# aspirin.net
KiCad netlist of a schematic drawn in EAGLE
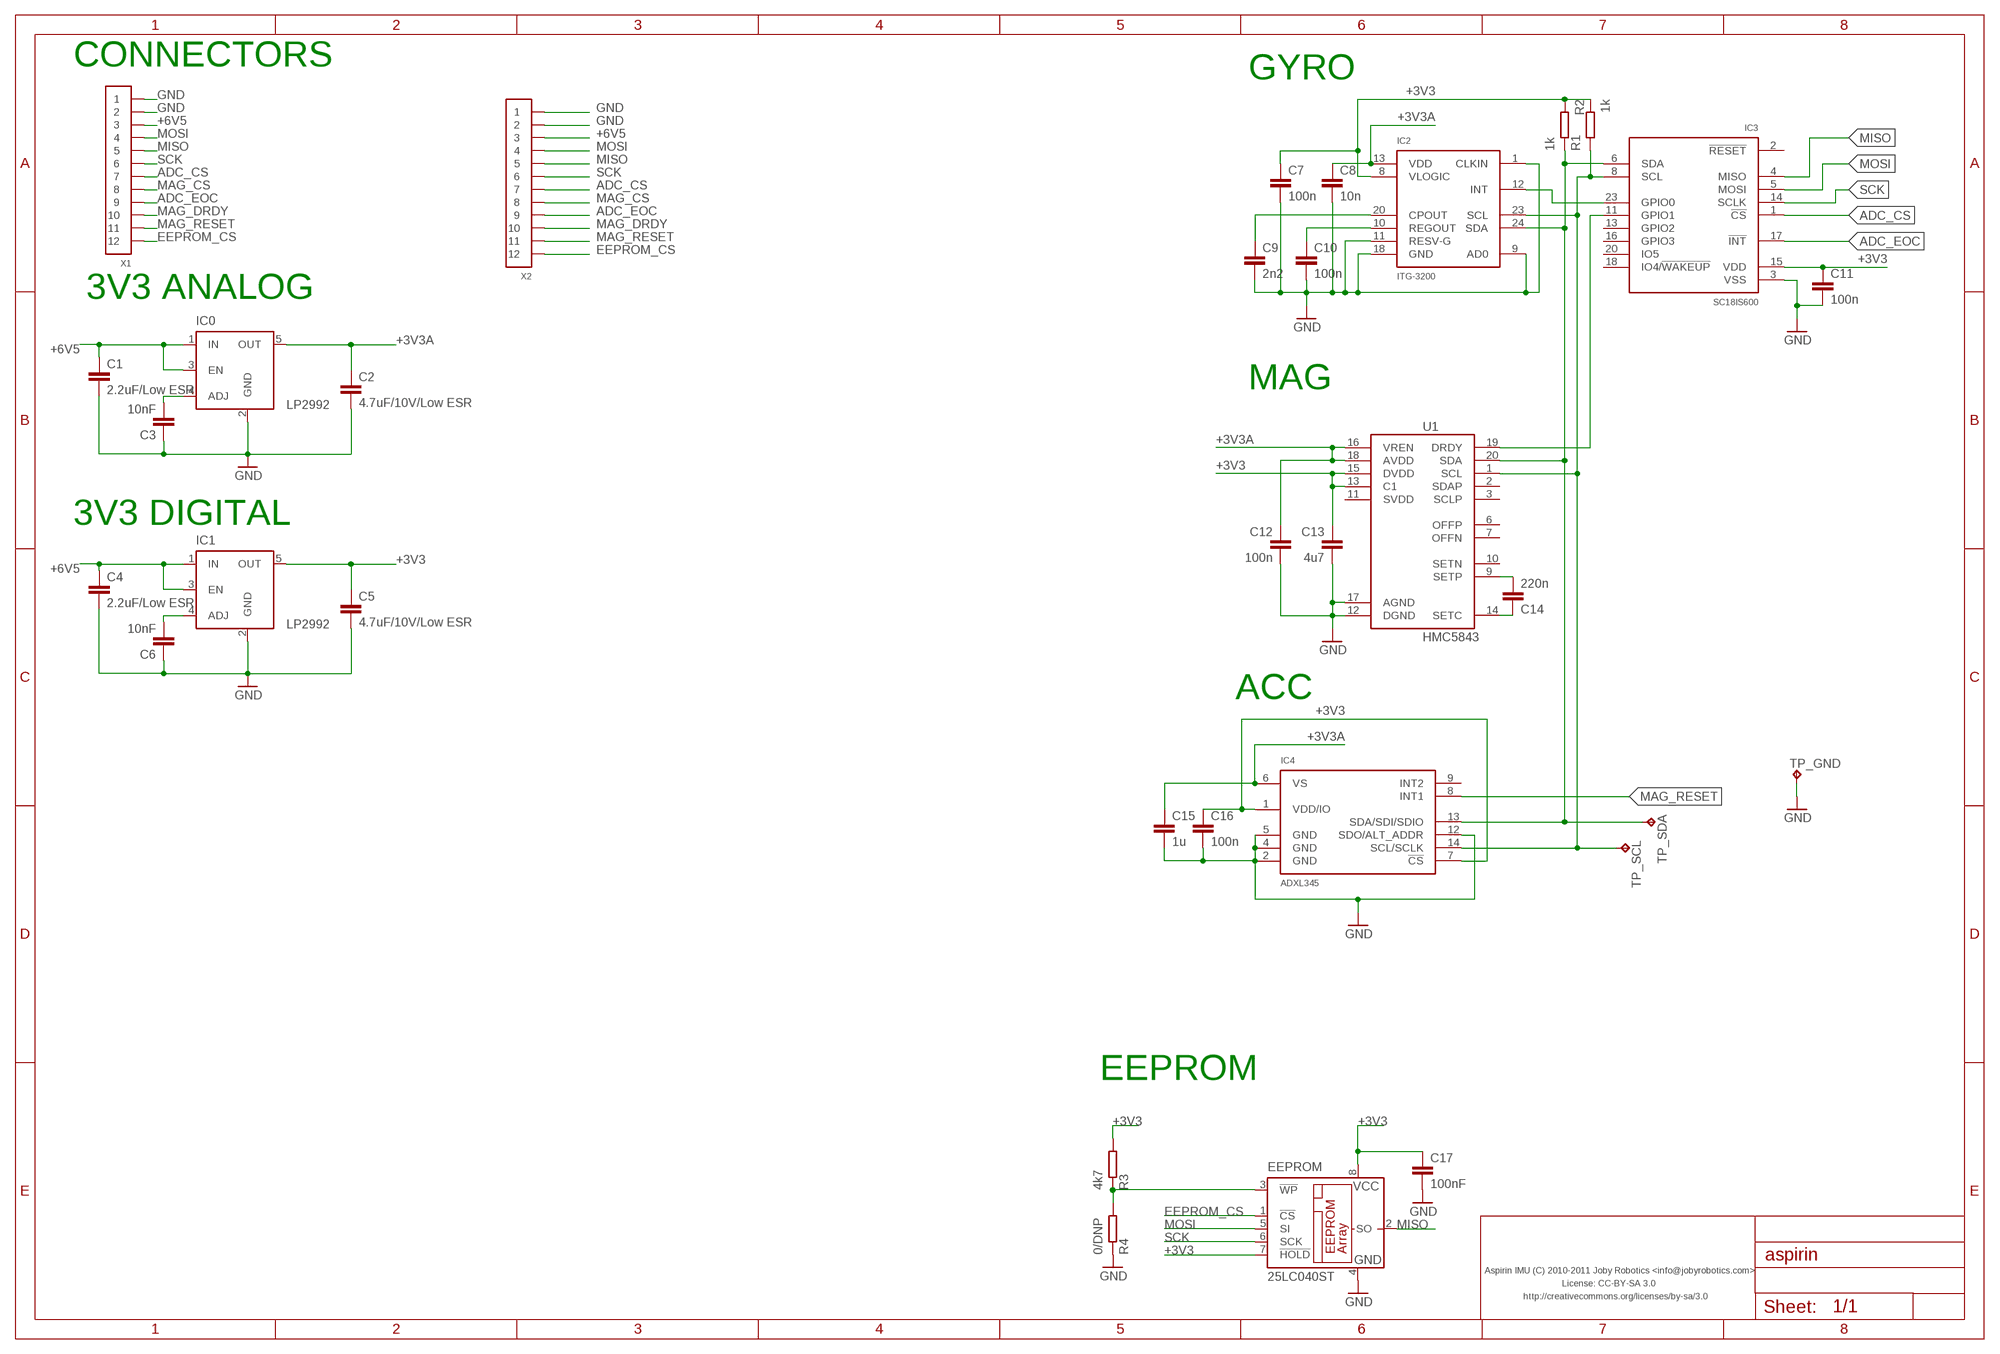
[diagram p0: schematic, sheet 1]

(export (version "E")
  (design (tool "Eeschema 10.0.6"))
  (components
    (comp (ref "C1")
      (value "2.2uF/Low ESR")
      (footprint "eagle-import:0603-CAP")
      (libsource (lib "eagle-import") (part "CAPACITOR-0603"))
    )
    (comp (ref "C2")
      (value "4.7uF/10V/Low ESR")
      (footprint "eagle-import:0603-CAP")
      (libsource (lib "eagle-import") (part "CAPACITOR-0603"))
    )
    (comp (ref "C3")
      (value "10nF")
      (footprint "eagle-import:0603-CAP")
      (libsource (lib "eagle-import") (part "CAPACITOR-0603"))
    )
    (comp (ref "C4")
      (value "2.2uF/Low ESR")
      (footprint "eagle-import:0603-CAP")
      (libsource (lib "eagle-import") (part "CAPACITOR-0603"))
    )
    (comp (ref "C5")
      (value "4.7uF/10V/Low ESR")
      (footprint "eagle-import:0603-CAP")
      (libsource (lib "eagle-import") (part "CAPACITOR-0603"))
    )
    (comp (ref "C6")
      (value "10nF")
      (footprint "eagle-import:0603-CAP")
      (libsource (lib "eagle-import") (part "CAPACITOR-0603"))
    )
    (comp (ref "C7")
      (value "100n")
      (footprint "eagle-import:0603-CAP")
      (libsource (lib "eagle-import") (part "CAPACITOR-0603"))
    )
    (comp (ref "C8")
      (value "10n")
      (footprint "eagle-import:0603-CAP")
      (libsource (lib "eagle-import") (part "CAPACITOR-0603"))
    )
    (comp (ref "C9")
      (value "2n2")
      (footprint "eagle-import:0603-CAP")
      (libsource (lib "eagle-import") (part "CAPACITOR-0603"))
    )
    (comp (ref "C10")
      (value "100n")
      (footprint "eagle-import:0603-CAP")
      (libsource (lib "eagle-import") (part "CAPACITOR-0603"))
    )
    (comp (ref "C11")
      (value "100n")
      (footprint "eagle-import:0603-CAP")
      (libsource (lib "eagle-import") (part "CAPACITOR-0603"))
    )
    (comp (ref "C12")
      (value "100n")
      (footprint "eagle-import:0603-CAP")
      (libsource (lib "eagle-import") (part "CAPACITOR-0603"))
    )
    (comp (ref "C13")
      (value "4u7")
      (footprint "eagle-import:0603-CAP")
      (libsource (lib "eagle-import") (part "CAPACITOR-0603"))
    )
    (comp (ref "C14")
      (value "220n")
      (footprint "eagle-import:0603-CAP")
      (libsource (lib "eagle-import") (part "CAPACITOR-0603"))
    )
    (comp (ref "C15")
      (value "1u")
      (footprint "eagle-import:0603-CAP")
      (libsource (lib "eagle-import") (part "CAPACITOR-0603"))
    )
    (comp (ref "C16")
      (value "100n")
      (footprint "eagle-import:0603-CAP")
      (libsource (lib "eagle-import") (part "CAPACITOR-0603"))
    )
    (comp (ref "C17")
      (value "100nF")
      (footprint "eagle-import:0603-CAP")
      (libsource (lib "eagle-import") (part "CAPACITOR-0603"))
    )
    (comp (ref "EEPROM")
      (value "25LC040ST")
      (footprint "eagle-import:TSSOP8")
      (libsource (lib "eagle-import") (part "25STLC040"))
    )
    (comp (ref "IC0")
      (value "LP2992")
      (footprint "eagle-import:SOT23-5")
      (libsource (lib "eagle-import") (part "MIC5219BM5"))
    )
    (comp (ref "IC1")
      (value "LP2992")
      (footprint "eagle-import:SOT23-5")
      (libsource (lib "eagle-import") (part "MIC5219BM5"))
    )
    (comp (ref "IC2")
      (value "ITG-3200")
      (footprint "eagle-import:QFN24-WITH-AXES")
      (libsource (lib "eagle-import") (part "ITG-3200-AX"))
    )
    (comp (ref "IC3")
      (value "SC18IS600")
      (footprint "eagle-import:QFN24")
      (libsource (lib "eagle-import") (part "SC18IS600"))
    )
    (comp (ref "IC4")
      (value "ADXL345")
      (footprint "eagle-import:LGA-14")
      (libsource (lib "eagle-import") (part "ADXL345"))
    )
    (comp (ref "R1")
      (value "1k")
      (footprint "eagle-import:0603-RES")
      (libsource (lib "eagle-import") (part "RESISTOR-0603"))
    )
    (comp (ref "R2")
      (value "1k")
      (footprint "eagle-import:0603-RES")
      (libsource (lib "eagle-import") (part "RESISTOR-0603"))
    )
    (comp (ref "R3")
      (value "4k7")
      (footprint "eagle-import:0603-RES")
      (libsource (lib "eagle-import") (part "RESISTOR-0603"))
    )
    (comp (ref "R4")
      (value "0/DNP")
      (footprint "eagle-import:0603-RES")
      (libsource (lib "eagle-import") (part "RESISTOR-0603"))
    )
    (comp (ref "TP_GND")
      (value "TP-SMD")
      (footprint "eagle-import:MINI_TESTPAD")
      (libsource (lib "eagle-import") (part "TP-SMD"))
    )
    (comp (ref "TP_SCL")
      (value "TP-SMD")
      (footprint "eagle-import:MINI_TESTPAD")
      (libsource (lib "eagle-import") (part "TP-SMD"))
    )
    (comp (ref "TP_SDA")
      (value "TP-SMD")
      (footprint "eagle-import:MINI_TESTPAD")
      (libsource (lib "eagle-import") (part "TP-SMD"))
    )
    (comp (ref "U1")
      (value "HMC5843")
      (footprint "eagle-import:LPCC20-HMC5843")
      (libsource (lib "eagle-import") (part "HMC5843"))
    )
    (comp (ref "X1")
      (value "CONN_12-1-53047")
      (footprint "eagle-import:PB-53047-12")
      (libsource (lib "eagle-import") (part "CONN_12-1-53047"))
    )
    (comp (ref "X2")
      (value "CONN_12-1-53261")
      (footprint "eagle-import:PB-53261-12")
      (libsource (lib "eagle-import") (part "CONN_12-1-53261"))
    )
  )
  (nets
    (net (code "1") (name "/+3V3") (class "Default")
      (node (ref "C11") (pin "P$1") (pinfunction "1_P$1") (pintype "passive"))
      (node (ref "C13") (pin "P$1") (pinfunction "1_P$1") (pintype "passive"))
      (node (ref "C16") (pin "P$1") (pinfunction "1_P$1") (pintype "passive"))
      (node (ref "C17") (pin "P$1") (pinfunction "1_P$1") (pintype "passive"))
      (node (ref "C5") (pin "P$1") (pinfunction "1_P$1") (pintype "passive"))
      (node (ref "C7") (pin "P$1") (pinfunction "1_P$1") (pintype "passive"))
      (node (ref "EEPROM") (pin "7") (pinfunction "~{HOLD}_7") (pintype "input"))
      (node (ref "EEPROM") (pin "8") (pinfunction "VCC_8") (pintype "power_in"))
      (node (ref "IC1") (pin "5") (pinfunction "OUT_5") (pintype "output"))
      (node (ref "IC2") (pin "8") (pinfunction "VLOGIC_8") (pintype "bidirectional"))
      (node (ref "IC3") (pin "15") (pinfunction "VDD_15") (pintype "bidirectional"))
      (node (ref "IC4") (pin "1") (pinfunction "VDD/IO_1") (pintype "bidirectional"))
      (node (ref "IC4") (pin "7") (pinfunction "~{CS}_7") (pintype "bidirectional"))
      (node (ref "R1") (pin "P$2") (pinfunction "2_P$2") (pintype "passive"))
      (node (ref "R2") (pin "P$1") (pinfunction "1_P$1") (pintype "passive"))
      (node (ref "R3") (pin "P$2") (pinfunction "2_P$2") (pintype "passive"))
      (node (ref "U1") (pin "13") (pinfunction "C1_13") (pintype "bidirectional"))
      (node (ref "U1") (pin "15") (pinfunction "DVDD_15") (pintype "bidirectional"))
    )
    (net (code "2") (name "/+3V3A") (class "Default")
      (node (ref "C12") (pin "P$1") (pinfunction "1_P$1") (pintype "passive"))
      (node (ref "C15") (pin "P$1") (pinfunction "1_P$1") (pintype "passive"))
      (node (ref "C2") (pin "P$1") (pinfunction "1_P$1") (pintype "passive"))
      (node (ref "C8") (pin "P$1") (pinfunction "1_P$1") (pintype "passive"))
      (node (ref "IC0") (pin "5") (pinfunction "OUT_5") (pintype "output"))
      (node (ref "IC2") (pin "13") (pinfunction "VDD_13") (pintype "bidirectional"))
      (node (ref "IC4") (pin "6") (pinfunction "VS_6") (pintype "bidirectional"))
      (node (ref "U1") (pin "16") (pinfunction "VREN_16") (pintype "bidirectional"))
      (node (ref "U1") (pin "18") (pinfunction "AVDD_18") (pintype "bidirectional"))
    )
    (net (code "3") (name "/+6V5") (class "Default")
      (node (ref "C1") (pin "P$1") (pinfunction "1_P$1") (pintype "passive"))
      (node (ref "C4") (pin "P$1") (pinfunction "1_P$1") (pintype "passive"))
      (node (ref "IC0") (pin "1") (pinfunction "IN_1") (pintype "input"))
      (node (ref "IC0") (pin "3") (pinfunction "EN_3") (pintype "input"))
      (node (ref "IC1") (pin "1") (pinfunction "IN_1") (pintype "input"))
      (node (ref "IC1") (pin "3") (pinfunction "EN_3") (pintype "input"))
      (node (ref "X1") (pin "3") (pinfunction "3_3") (pintype "bidirectional"))
      (node (ref "X2") (pin "3") (pinfunction "3_3") (pintype "bidirectional"))
    )
    (net (code "4") (name "/EEPROM_CS") (class "Default")
      (node (ref "EEPROM") (pin "1") (pinfunction "~{CS}_1") (pintype "input"))
      (node (ref "X1") (pin "12") (pinfunction "12_12") (pintype "bidirectional"))
      (node (ref "X2") (pin "12") (pinfunction "12_12") (pintype "bidirectional"))
    )
    (net (code "5") (name "/MAG_CS") (class "Default")
      (node (ref "IC2") (pin "12") (pinfunction "INT_12") (pintype "bidirectional"))
      (node (ref "IC3") (pin "23") (pinfunction "GPIO0_23") (pintype "bidirectional"))
      (node (ref "X1") (pin "8") (pinfunction "8_8") (pintype "bidirectional"))
      (node (ref "X2") (pin "8") (pinfunction "8_8") (pintype "bidirectional"))
    )
    (net (code "6") (name "/MAG_DRDY") (class "Default")
      (node (ref "IC3") (pin "11") (pinfunction "GPIO1_11") (pintype "bidirectional"))
      (node (ref "U1") (pin "19") (pinfunction "DRDY_19") (pintype "bidirectional"))
      (node (ref "X1") (pin "10") (pinfunction "10_10") (pintype "bidirectional"))
      (node (ref "X2") (pin "10") (pinfunction "10_10") (pintype "bidirectional"))
    )
    (net (code "7") (name "ADC_CS") (class "Default")
      (node (ref "IC3") (pin "1") (pinfunction "~{CS}_1") (pintype "bidirectional"))
      (node (ref "X1") (pin "7") (pinfunction "7_7") (pintype "bidirectional"))
      (node (ref "X2") (pin "7") (pinfunction "7_7") (pintype "bidirectional"))
    )
    (net (code "8") (name "ADC_EOC") (class "Default")
      (node (ref "IC3") (pin "17") (pinfunction "~{INT}_17") (pintype "bidirectional"))
      (node (ref "X1") (pin "9") (pinfunction "9_9") (pintype "bidirectional"))
      (node (ref "X2") (pin "9") (pinfunction "9_9") (pintype "bidirectional"))
    )
    (net (code "9") (name "GND") (class "Default")
      (node (ref "C1") (pin "P$2") (pinfunction "2_P$2") (pintype "passive"))
      (node (ref "C10") (pin "P$2") (pinfunction "2_P$2") (pintype "passive"))
      (node (ref "C11") (pin "P$2") (pinfunction "2_P$2") (pintype "passive"))
      (node (ref "C12") (pin "P$2") (pinfunction "2_P$2") (pintype "passive"))
      (node (ref "C13") (pin "P$2") (pinfunction "2_P$2") (pintype "passive"))
      (node (ref "C15") (pin "P$2") (pinfunction "2_P$2") (pintype "passive"))
      (node (ref "C16") (pin "P$2") (pinfunction "2_P$2") (pintype "passive"))
      (node (ref "C17") (pin "P$2") (pinfunction "2_P$2") (pintype "passive"))
      (node (ref "C2") (pin "P$2") (pinfunction "2_P$2") (pintype "passive"))
      (node (ref "C3") (pin "P$1") (pinfunction "1_P$1") (pintype "passive"))
      (node (ref "C4") (pin "P$2") (pinfunction "2_P$2") (pintype "passive"))
      (node (ref "C5") (pin "P$2") (pinfunction "2_P$2") (pintype "passive"))
      (node (ref "C6") (pin "P$1") (pinfunction "1_P$1") (pintype "passive"))
      (node (ref "C7") (pin "P$2") (pinfunction "2_P$2") (pintype "passive"))
      (node (ref "C8") (pin "P$2") (pinfunction "2_P$2") (pintype "passive"))
      (node (ref "C9") (pin "P$2") (pinfunction "2_P$2") (pintype "passive"))
      (node (ref "EEPROM") (pin "4") (pinfunction "GND_4") (pintype "power_in"))
      (node (ref "IC0") (pin "2") (pinfunction "GND_2") (pintype "power_in"))
      (node (ref "IC1") (pin "2") (pinfunction "GND_2") (pintype "power_in"))
      (node (ref "IC2") (pin "1") (pinfunction "CLKIN_1") (pintype "bidirectional"))
      (node (ref "IC2") (pin "11") (pinfunction "RESV-G_11") (pintype "bidirectional"))
      (node (ref "IC2") (pin "18") (pinfunction "GND_18") (pintype "bidirectional"))
      (node (ref "IC2") (pin "9") (pinfunction "AD0_9") (pintype "bidirectional"))
      (node (ref "IC3") (pin "3") (pinfunction "VSS_3") (pintype "bidirectional"))
      (node (ref "IC4") (pin "12") (pinfunction "SDO/ALT_ADDR_12") (pintype "bidirectional"))
      (node (ref "IC4") (pin "2") (pinfunction "GND_2") (pintype "bidirectional"))
      (node (ref "IC4") (pin "4") (pinfunction "GND_4") (pintype "bidirectional"))
      (node (ref "IC4") (pin "5") (pinfunction "GND_5") (pintype "bidirectional"))
      (node (ref "R4") (pin "P$1") (pinfunction "1_P$1") (pintype "passive"))
      (node (ref "TP_GND") (pin "1") (pinfunction "TP_1") (pintype "input"))
      (node (ref "U1") (pin "12") (pinfunction "DGND_12") (pintype "bidirectional"))
      (node (ref "U1") (pin "17") (pinfunction "AGND_17") (pintype "bidirectional"))
      (node (ref "X1") (pin "1") (pinfunction "1_1") (pintype "bidirectional"))
      (node (ref "X1") (pin "2") (pinfunction "2_2") (pintype "bidirectional"))
      (node (ref "X2") (pin "1") (pinfunction "1_1") (pintype "bidirectional"))
      (node (ref "X2") (pin "2") (pinfunction "2_2") (pintype "bidirectional"))
    )
    (net (code "10") (name "MAG_RESET") (class "Default")
      (node (ref "IC4") (pin "8") (pinfunction "INT1_8") (pintype "bidirectional"))
      (node (ref "X1") (pin "11") (pinfunction "11_11") (pintype "bidirectional"))
      (node (ref "X2") (pin "11") (pinfunction "11_11") (pintype "bidirectional"))
    )
    (net (code "11") (name "MISO") (class "Default")
      (node (ref "EEPROM") (pin "2") (pinfunction "SO_2") (pintype "bidirectional"))
      (node (ref "IC3") (pin "4") (pinfunction "MISO_4") (pintype "bidirectional"))
      (node (ref "X1") (pin "5") (pinfunction "5_5") (pintype "bidirectional"))
      (node (ref "X2") (pin "5") (pinfunction "5_5") (pintype "bidirectional"))
    )
    (net (code "12") (name "MOSI") (class "Default")
      (node (ref "EEPROM") (pin "5") (pinfunction "SI_5") (pintype "input"))
      (node (ref "IC3") (pin "5") (pinfunction "MOSI_5") (pintype "bidirectional"))
      (node (ref "X1") (pin "4") (pinfunction "4_4") (pintype "bidirectional"))
      (node (ref "X2") (pin "4") (pinfunction "4_4") (pintype "bidirectional"))
    )
    (net (code "13") (name "Net-(C3-2)") (class "Default")
      (node (ref "C3") (pin "P$2") (pinfunction "2_P$2") (pintype "passive"))
      (node (ref "IC0") (pin "4") (pinfunction "ADJ_4") (pintype "passive"))
    )
    (net (code "14") (name "Net-(C6-2)") (class "Default")
      (node (ref "C6") (pin "P$2") (pinfunction "2_P$2") (pintype "passive"))
      (node (ref "IC1") (pin "4") (pinfunction "ADJ_4") (pintype "passive"))
    )
    (net (code "15") (name "Net-(C9-1)") (class "Default")
      (node (ref "C9") (pin "P$1") (pinfunction "1_P$1") (pintype "passive"))
      (node (ref "IC2") (pin "20") (pinfunction "CPOUT_20") (pintype "bidirectional"))
    )
    (net (code "16") (name "Net-(C10-1)") (class "Default")
      (node (ref "C10") (pin "P$1") (pinfunction "1_P$1") (pintype "passive"))
      (node (ref "IC2") (pin "10") (pinfunction "REGOUT_10") (pintype "bidirectional"))
    )
    (net (code "17") (name "Net-(C14-1)") (class "Default")
      (node (ref "C14") (pin "P$1") (pinfunction "1_P$1") (pintype "passive"))
      (node (ref "U1") (pin "14") (pinfunction "SETC_14") (pintype "bidirectional"))
    )
    (net (code "18") (name "Net-(C14-2)") (class "Default")
      (node (ref "C14") (pin "P$2") (pinfunction "2_P$2") (pintype "passive"))
      (node (ref "U1") (pin "9") (pinfunction "SETP_9") (pintype "bidirectional"))
    )
    (net (code "19") (name "Net-(EEPROM-~{WP})") (class "Default")
      (node (ref "EEPROM") (pin "3") (pinfunction "~{WP}_3") (pintype "input"))
      (node (ref "R3") (pin "P$1") (pinfunction "1_P$1") (pintype "passive"))
      (node (ref "R4") (pin "P$2") (pinfunction "2_P$2") (pintype "passive"))
    )
    (net (code "20") (name "Net-(IC2-SCL)") (class "Default")
      (node (ref "IC2") (pin "23") (pinfunction "SCL_23") (pintype "bidirectional"))
      (node (ref "IC3") (pin "8") (pinfunction "SCL_8") (pintype "bidirectional"))
      (node (ref "IC4") (pin "14") (pinfunction "SCL/SCLK_14") (pintype "bidirectional"))
      (node (ref "R2") (pin "P$2") (pinfunction "2_P$2") (pintype "passive"))
      (node (ref "TP_SCL") (pin "1") (pinfunction "TP_1") (pintype "input"))
      (node (ref "U1") (pin "1") (pinfunction "SCL_1") (pintype "bidirectional"))
    )
    (net (code "21") (name "Net-(IC2-SDA)") (class "Default")
      (node (ref "IC2") (pin "24") (pinfunction "SDA_24") (pintype "bidirectional"))
      (node (ref "IC3") (pin "6") (pinfunction "SDA_6") (pintype "bidirectional"))
      (node (ref "IC4") (pin "13") (pinfunction "SDA/SDI/SDIO_13") (pintype "bidirectional"))
      (node (ref "R1") (pin "P$1") (pinfunction "1_P$1") (pintype "passive"))
      (node (ref "TP_SDA") (pin "1") (pinfunction "TP_1") (pintype "input"))
      (node (ref "U1") (pin "20") (pinfunction "SDA_20") (pintype "bidirectional"))
    )
    (net (code "22") (name "SCK") (class "Default")
      (node (ref "EEPROM") (pin "6") (pinfunction "SCK_6") (pintype "input"))
      (node (ref "IC3") (pin "14") (pinfunction "SCLK_14") (pintype "bidirectional"))
      (node (ref "X1") (pin "6") (pinfunction "6_6") (pintype "bidirectional"))
      (node (ref "X2") (pin "6") (pinfunction "6_6") (pintype "bidirectional"))
    )
    (net (code "23") (name "unconnected-(IC3-GPIO2-Pad13)") (class "Default")
      (node (ref "IC3") (pin "13") (pinfunction "GPIO2_13") (pintype "bidirectional"))
    )
    (net (code "24") (name "unconnected-(IC3-GPIO3-Pad16)") (class "Default")
      (node (ref "IC3") (pin "16") (pinfunction "GPIO3_16") (pintype "bidirectional"))
    )
    (net (code "25") (name "unconnected-(IC3-IO4{slash}~{WAKEUP}-Pad18)") (class "Default")
      (node (ref "IC3") (pin "18") (pinfunction "IO4/~{WAKEUP}_18") (pintype "bidirectional"))
    )
    (net (code "26") (name "unconnected-(IC3-IO5-Pad20)") (class "Default")
      (node (ref "IC3") (pin "20") (pinfunction "IO5_20") (pintype "bidirectional"))
    )
    (net (code "27") (name "unconnected-(IC3-~{RESET}-Pad2)") (class "Default")
      (node (ref "IC3") (pin "2") (pinfunction "~{RESET}_2") (pintype "bidirectional"))
    )
    (net (code "28") (name "unconnected-(IC4-INT2-Pad9)") (class "Default")
      (node (ref "IC4") (pin "9") (pinfunction "INT2_9") (pintype "bidirectional"))
    )
    (net (code "29") (name "unconnected-(U1-OFFN-Pad7)") (class "Default")
      (node (ref "U1") (pin "7") (pinfunction "OFFN_7") (pintype "bidirectional"))
    )
    (net (code "30") (name "unconnected-(U1-OFFP-Pad6)") (class "Default")
      (node (ref "U1") (pin "6") (pinfunction "OFFP_6") (pintype "bidirectional"))
    )
    (net (code "31") (name "unconnected-(U1-SCLP-Pad3)") (class "Default")
      (node (ref "U1") (pin "3") (pinfunction "SCLP_3") (pintype "bidirectional"))
    )
    (net (code "32") (name "unconnected-(U1-SDAP-Pad2)") (class "Default")
      (node (ref "U1") (pin "2") (pinfunction "SDAP_2") (pintype "bidirectional"))
    )
    (net (code "33") (name "unconnected-(U1-SETN-Pad10)") (class "Default")
      (node (ref "U1") (pin "10") (pinfunction "SETN_10") (pintype "bidirectional"))
    )
    (net (code "34") (name "unconnected-(U1-SVDD-Pad11)") (class "Default")
      (node (ref "U1") (pin "11") (pinfunction "SVDD_11") (pintype "bidirectional"))
    )
  )
)
